# iForgeHat.net
KiCad netlist of a schematic drawn in EAGLE
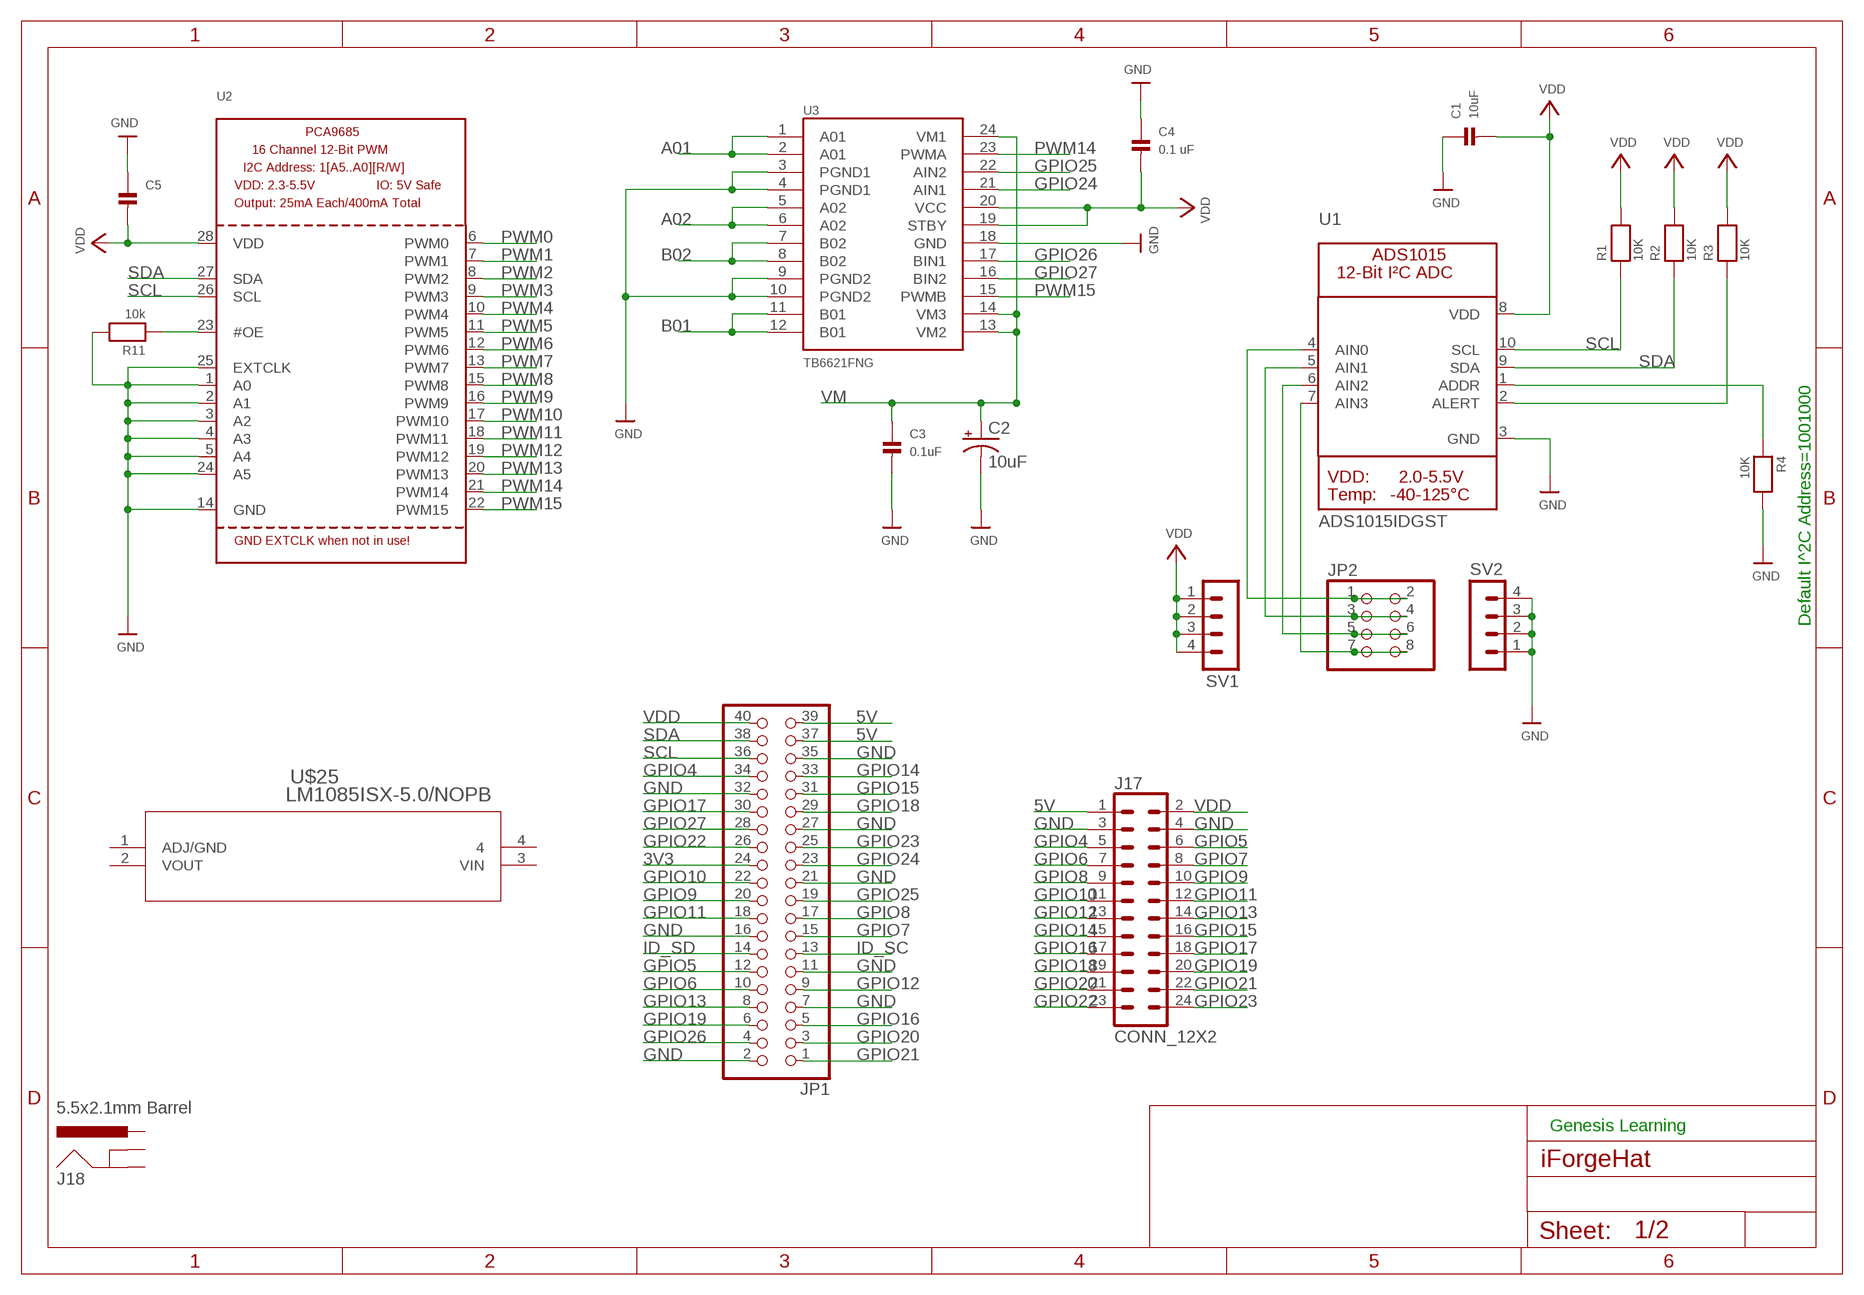
[diagram p0: schematic, sheet 1]
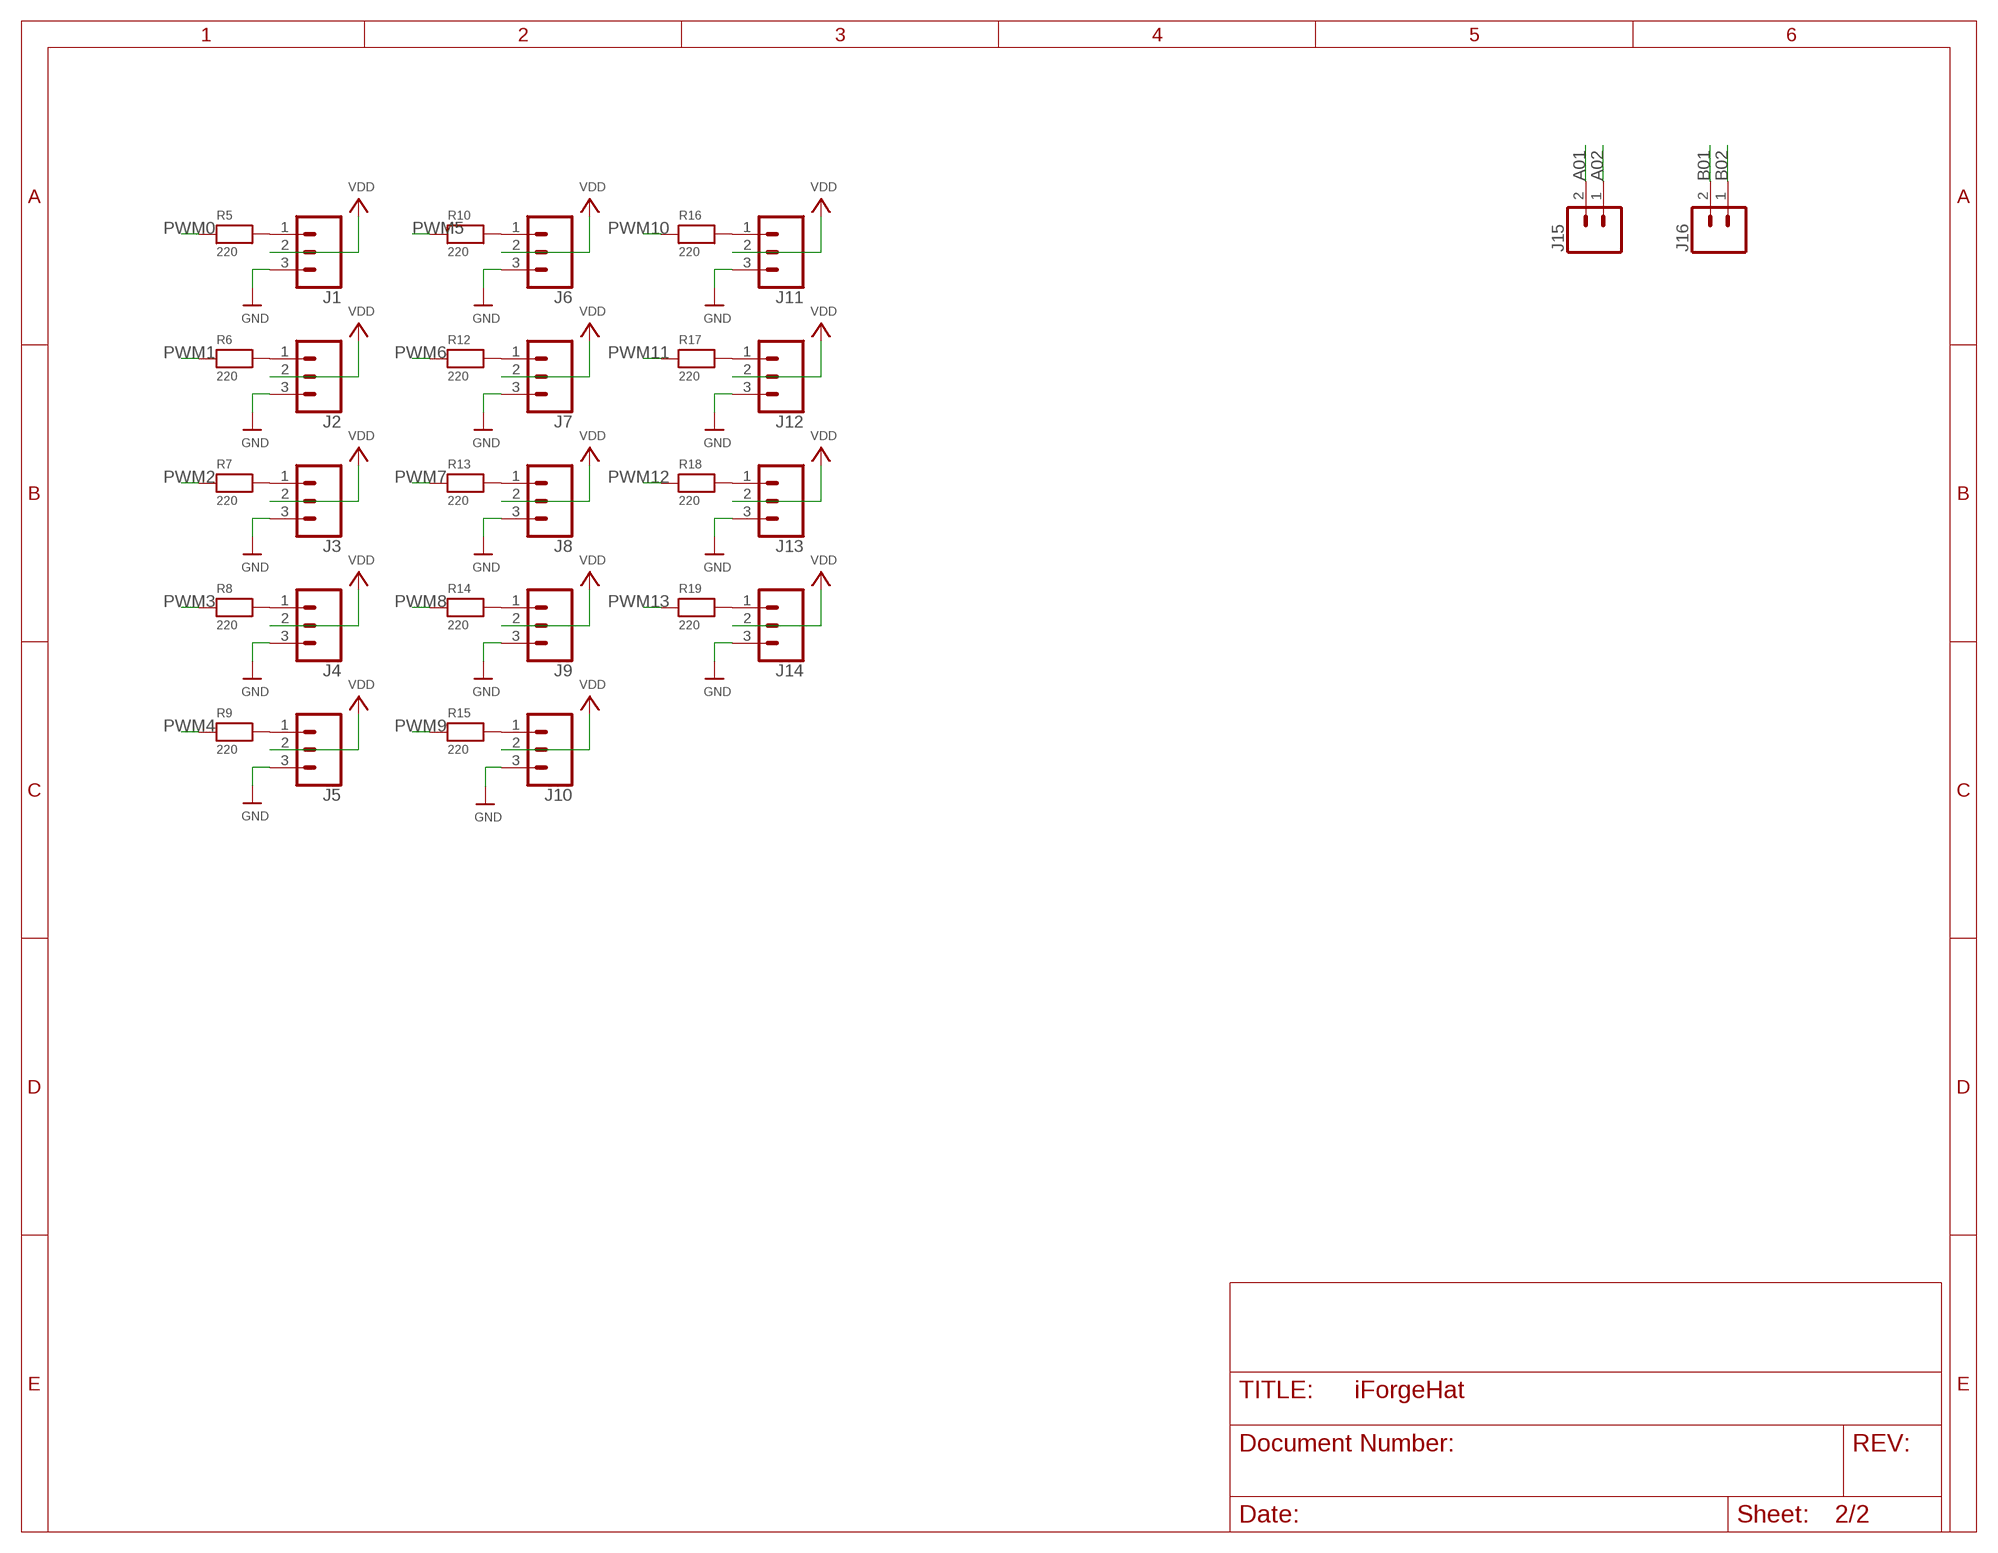
[diagram p1: schematic, sheet 2]

(export (version "E")
  (design (tool "Eeschema 10.0.6"))
  (components
    (comp (ref "J1")
      (value "CONN_03")
      (footprint "eagle-import:1X03")
      (libsource (lib "eagle-import") (part "CONN_03"))
    )
    (comp (ref "J2")
      (value "CONN_03")
      (footprint "eagle-import:1X03")
      (libsource (lib "eagle-import") (part "CONN_03"))
    )
    (comp (ref "J3")
      (value "CONN_03")
      (footprint "eagle-import:1X03")
      (libsource (lib "eagle-import") (part "CONN_03"))
    )
    (comp (ref "J4")
      (value "CONN_03")
      (footprint "eagle-import:1X03")
      (libsource (lib "eagle-import") (part "CONN_03"))
    )
    (comp (ref "J5")
      (value "CONN_03")
      (footprint "eagle-import:1X03")
      (libsource (lib "eagle-import") (part "CONN_03"))
    )
    (comp (ref "J6")
      (value "CONN_03")
      (footprint "eagle-import:1X03")
      (libsource (lib "eagle-import") (part "CONN_03"))
    )
    (comp (ref "J7")
      (value "CONN_03")
      (footprint "eagle-import:1X03")
      (libsource (lib "eagle-import") (part "CONN_03"))
    )
    (comp (ref "J8")
      (value "CONN_03")
      (footprint "eagle-import:1X03")
      (libsource (lib "eagle-import") (part "CONN_03"))
    )
    (comp (ref "J9")
      (value "CONN_03")
      (footprint "eagle-import:1X03")
      (libsource (lib "eagle-import") (part "CONN_03"))
    )
    (comp (ref "J10")
      (value "CONN_03")
      (footprint "eagle-import:1X03")
      (libsource (lib "eagle-import") (part "CONN_03"))
    )
    (comp (ref "J11")
      (value "CONN_03")
      (footprint "eagle-import:1X03")
      (libsource (lib "eagle-import") (part "CONN_03"))
    )
    (comp (ref "J12")
      (value "CONN_03")
      (footprint "eagle-import:1X03")
      (libsource (lib "eagle-import") (part "CONN_03"))
    )
    (comp (ref "J13")
      (value "CONN_03")
      (footprint "eagle-import:1X03")
      (libsource (lib "eagle-import") (part "CONN_03"))
    )
    (comp (ref "J14")
      (value "CONN_03")
      (footprint "eagle-import:1X03")
      (libsource (lib "eagle-import") (part "CONN_03"))
    )
    (comp (ref "J15")
      (value "CONN_02SPRING-2.54-RA")
      (footprint "eagle-import:SPRINGTERMINAL-2.54MM-2")
      (libsource (lib "eagle-import") (part "CONN_02SPRING-2.54-RA"))
    )
    (comp (ref "J16")
      (value "CONN_02SPRING-2.54-RA")
      (footprint "eagle-import:SPRINGTERMINAL-2.54MM-2")
      (libsource (lib "eagle-import") (part "CONN_02SPRING-2.54-RA"))
    )
    (comp (ref "R5")
      (value "220")
      (footprint "eagle-import:0402")
      (libsource (lib "eagle-import") (part "RESISTOR0402"))
    )
    (comp (ref "R6")
      (value "220")
      (footprint "eagle-import:0402")
      (libsource (lib "eagle-import") (part "RESISTOR0402"))
    )
    (comp (ref "R7")
      (value "220")
      (footprint "eagle-import:0402")
      (libsource (lib "eagle-import") (part "RESISTOR0402"))
    )
    (comp (ref "R8")
      (value "220")
      (footprint "eagle-import:0402")
      (libsource (lib "eagle-import") (part "RESISTOR0402"))
    )
    (comp (ref "R9")
      (value "220")
      (footprint "eagle-import:0402")
      (libsource (lib "eagle-import") (part "RESISTOR0402"))
    )
    (comp (ref "R10")
      (value "220")
      (footprint "eagle-import:0402")
      (libsource (lib "eagle-import") (part "RESISTOR0402"))
    )
    (comp (ref "R12")
      (value "220")
      (footprint "eagle-import:0402")
      (libsource (lib "eagle-import") (part "RESISTOR0402"))
    )
    (comp (ref "R13")
      (value "220")
      (footprint "eagle-import:0402")
      (libsource (lib "eagle-import") (part "RESISTOR0402"))
    )
    (comp (ref "R14")
      (value "220")
      (footprint "eagle-import:0402")
      (libsource (lib "eagle-import") (part "RESISTOR0402"))
    )
    (comp (ref "R15")
      (value "220")
      (footprint "eagle-import:0402")
      (libsource (lib "eagle-import") (part "RESISTOR0402"))
    )
    (comp (ref "R16")
      (value "220")
      (footprint "eagle-import:0402")
      (libsource (lib "eagle-import") (part "RESISTOR0402"))
    )
    (comp (ref "R17")
      (value "220")
      (footprint "eagle-import:0402")
      (libsource (lib "eagle-import") (part "RESISTOR0402"))
    )
    (comp (ref "R18")
      (value "220")
      (footprint "eagle-import:0402")
      (libsource (lib "eagle-import") (part "RESISTOR0402"))
    )
    (comp (ref "R19")
      (value "220")
      (footprint "eagle-import:0402")
      (libsource (lib "eagle-import") (part "RESISTOR0402"))
    )
    (comp (ref "C1")
      (value "10uF")
      (footprint "eagle-import:0402")
      (libsource (lib "eagle-import") (part "CAP_CERAMIC0402"))
    )
    (comp (ref "C2")
      (value "10uF")
      (footprint "eagle-import:414-VA5R")
      (libsource (lib "eagle-import") (part "SUPERCAP"))
    )
    (comp (ref "C3")
      (value "0.1uF")
      (footprint "eagle-import:0402")
      (libsource (lib "eagle-import") (part "CAP_CERAMIC0402"))
    )
    (comp (ref "C4")
      (value "0.1 uF")
      (footprint "eagle-import:0402")
      (libsource (lib "eagle-import") (part "CAP_CERAMIC0402"))
    )
    (comp (ref "C5")
      (value "CAP_CERAMIC0402")
      (footprint "eagle-import:0402")
      (libsource (lib "eagle-import") (part "CAP_CERAMIC0402"))
    )
    (comp (ref "J17")
      (value "CONN_12X2")
      (footprint "eagle-import:2X12")
      (libsource (lib "eagle-import") (part "CONN_12X2"))
    )
    (comp (ref "J18")
      (value "5.5x2.1mm Barrel")
      (footprint "eagle-import:POWER_JACK_SMD")
      (libsource (lib "eagle-import") (part "POWER_JACKSMD"))
    )
    (comp (ref "JP1")
      (value "PINHD-2X20")
      (footprint "eagle-import:2X20")
      (libsource (lib "eagle-import") (part "PINHD-2X20"))
    )
    (comp (ref "JP2")
      (value "PINHD-2X4")
      (footprint "eagle-import:2X04")
      (libsource (lib "eagle-import") (part "PINHD-2X4"))
    )
    (comp (ref "R1")
      (value "10K")
      (footprint "eagle-import:0402")
      (libsource (lib "eagle-import") (part "RESISTOR0402"))
    )
    (comp (ref "R2")
      (value "10K")
      (footprint "eagle-import:0402")
      (libsource (lib "eagle-import") (part "RESISTOR0402"))
    )
    (comp (ref "R3")
      (value "10K")
      (footprint "eagle-import:0402")
      (libsource (lib "eagle-import") (part "RESISTOR0402"))
    )
    (comp (ref "R4")
      (value "10K")
      (footprint "eagle-import:0402")
      (libsource (lib "eagle-import") (part "RESISTOR0402"))
    )
    (comp (ref "R11")
      (value "10k")
      (footprint "eagle-import:0402")
      (libsource (lib "eagle-import") (part "RESISTOR0402"))
    )
    (comp (ref "SV1")
      (value "MA04-1")
      (footprint "eagle-import:MA04-1")
      (libsource (lib "eagle-import") (part "MA04-1"))
    )
    (comp (ref "SV2")
      (value "MA04-1")
      (footprint "eagle-import:MA04-1")
      (libsource (lib "eagle-import") (part "MA04-1"))
    )
    (comp (ref "U$25")
      (value "LM1085ISX-5.0/NOPB")
      (footprint "eagle-import:TS3B")
      (fields (field (name "MANUFACTURER_PART_NUMBER") "LM1085ISX5.0NOPB"))
      (libsource (lib "eagle-import") (part "LM1085ISX-5.0/NOPB"))
    )
    (comp (ref "U1")
      (value "ADS1015IDGST")
      (footprint "eagle-import:MSOP10")
      (libsource (lib "eagle-import") (part "ADC_ADS1015"))
    )
    (comp (ref "U2")
      (value "PCA9685")
      (footprint "eagle-import:TSSOP28")
      (libsource (lib "eagle-import") (part "PCA9685"))
    )
    (comp (ref "U3")
      (value "TB6621FNG")
      (footprint "eagle-import:SSOP24")
      (libsource (lib "eagle-import") (part "TB6621FNG"))
    )
  )
  (nets
    (net (code "1") (name "3V3") (class "Default")
      (node (ref "JP1") (pin "24") (pinfunction "24_24") (pintype "passive"))
    )
    (net (code "2") (name "5V") (class "Default")
      (node (ref "J17") (pin "1") (pinfunction "1_1") (pintype "passive"))
      (node (ref "JP1") (pin "37") (pinfunction "37_37") (pintype "passive"))
      (node (ref "JP1") (pin "39") (pinfunction "39_39") (pintype "passive"))
    )
    (net (code "3") (name "A01") (class "Default")
      (node (ref "J15") (pin "2") (pinfunction "2_2") (pintype "passive"))
      (node (ref "U3") (pin "1") (pinfunction "A01_1") (pintype "bidirectional"))
      (node (ref "U3") (pin "2") (pinfunction "A01_2") (pintype "bidirectional"))
    )
    (net (code "4") (name "A02") (class "Default")
      (node (ref "J15") (pin "1") (pinfunction "1_1") (pintype "passive"))
      (node (ref "U3") (pin "5") (pinfunction "A02_5") (pintype "bidirectional"))
      (node (ref "U3") (pin "6") (pinfunction "A02_6") (pintype "bidirectional"))
    )
    (net (code "5") (name "B01") (class "Default")
      (node (ref "J16") (pin "2") (pinfunction "2_2") (pintype "passive"))
      (node (ref "U3") (pin "11") (pinfunction "B01_11") (pintype "bidirectional"))
      (node (ref "U3") (pin "12") (pinfunction "B01_12") (pintype "bidirectional"))
    )
    (net (code "6") (name "B02") (class "Default")
      (node (ref "J16") (pin "1") (pinfunction "1_1") (pintype "passive"))
      (node (ref "U3") (pin "7") (pinfunction "B02_7") (pintype "bidirectional"))
      (node (ref "U3") (pin "8") (pinfunction "B02_8") (pintype "bidirectional"))
    )
    (net (code "7") (name "GND") (class "Default")
      (node (ref "C1") (pin "1") (pinfunction "P$1_1") (pintype "passive"))
      (node (ref "C2") (pin "-") (pinfunction "-_-") (pintype "passive"))
      (node (ref "C3") (pin "2") (pinfunction "P$2_2") (pintype "passive"))
      (node (ref "C4") (pin "1") (pinfunction "P$1_1") (pintype "passive"))
      (node (ref "C5") (pin "1") (pinfunction "P$1_1") (pintype "passive"))
      (node (ref "J1") (pin "3") (pinfunction "3_3") (pintype "passive"))
      (node (ref "J10") (pin "3") (pinfunction "3_3") (pintype "passive"))
      (node (ref "J11") (pin "3") (pinfunction "3_3") (pintype "passive"))
      (node (ref "J12") (pin "3") (pinfunction "3_3") (pintype "passive"))
      (node (ref "J13") (pin "3") (pinfunction "3_3") (pintype "passive"))
      (node (ref "J14") (pin "3") (pinfunction "3_3") (pintype "passive"))
      (node (ref "J17") (pin "3") (pinfunction "3_3") (pintype "passive"))
      (node (ref "J17") (pin "4") (pinfunction "4_4") (pintype "passive"))
      (node (ref "J2") (pin "3") (pinfunction "3_3") (pintype "passive"))
      (node (ref "J3") (pin "3") (pinfunction "3_3") (pintype "passive"))
      (node (ref "J4") (pin "3") (pinfunction "3_3") (pintype "passive"))
      (node (ref "J5") (pin "3") (pinfunction "3_3") (pintype "passive"))
      (node (ref "J6") (pin "3") (pinfunction "3_3") (pintype "passive"))
      (node (ref "J7") (pin "3") (pinfunction "3_3") (pintype "passive"))
      (node (ref "J8") (pin "3") (pinfunction "3_3") (pintype "passive"))
      (node (ref "J9") (pin "3") (pinfunction "3_3") (pintype "passive"))
      (node (ref "JP1") (pin "11") (pinfunction "11_11") (pintype "passive"))
      (node (ref "JP1") (pin "16") (pinfunction "16_16") (pintype "passive"))
      (node (ref "JP1") (pin "2") (pinfunction "2_2") (pintype "passive"))
      (node (ref "JP1") (pin "21") (pinfunction "21_21") (pintype "passive"))
      (node (ref "JP1") (pin "27") (pinfunction "27_27") (pintype "passive"))
      (node (ref "JP1") (pin "32") (pinfunction "32_32") (pintype "passive"))
      (node (ref "JP1") (pin "35") (pinfunction "35_35") (pintype "passive"))
      (node (ref "JP1") (pin "7") (pinfunction "7_7") (pintype "passive"))
      (node (ref "R11") (pin "2") (pinfunction "2_2") (pintype "passive"))
      (node (ref "R4") (pin "2") (pinfunction "2_2") (pintype "passive"))
      (node (ref "SV2") (pin "1") (pinfunction "1_1") (pintype "passive"))
      (node (ref "SV2") (pin "2") (pinfunction "2_2") (pintype "passive"))
      (node (ref "SV2") (pin "3") (pinfunction "3_3") (pintype "passive"))
      (node (ref "SV2") (pin "4") (pinfunction "4_4") (pintype "passive"))
      (node (ref "U1") (pin "3") (pinfunction "GND_3") (pintype "bidirectional"))
      (node (ref "U2") (pin "1") (pinfunction "A0_1") (pintype "bidirectional"))
      (node (ref "U2") (pin "14") (pinfunction "GND_14") (pintype "power_in"))
      (node (ref "U2") (pin "2") (pinfunction "A1_2") (pintype "bidirectional"))
      (node (ref "U2") (pin "24") (pinfunction "A5_24") (pintype "bidirectional"))
      (node (ref "U2") (pin "25") (pinfunction "EXTCLK_25") (pintype "input"))
      (node (ref "U2") (pin "3") (pinfunction "A2_3") (pintype "bidirectional"))
      (node (ref "U2") (pin "4") (pinfunction "A3_4") (pintype "bidirectional"))
      (node (ref "U2") (pin "5") (pinfunction "A4_5") (pintype "bidirectional"))
      (node (ref "U3") (pin "10") (pinfunction "PGND2_10") (pintype "bidirectional"))
      (node (ref "U3") (pin "18") (pinfunction "GND_18") (pintype "bidirectional"))
      (node (ref "U3") (pin "3") (pinfunction "PGND1_3") (pintype "bidirectional"))
      (node (ref "U3") (pin "4") (pinfunction "PGND1_4") (pintype "bidirectional"))
      (node (ref "U3") (pin "9") (pinfunction "PGND2_9") (pintype "bidirectional"))
    )
    (net (code "8") (name "GPIO4") (class "Default")
      (node (ref "J17") (pin "5") (pinfunction "5_5") (pintype "passive"))
      (node (ref "JP1") (pin "34") (pinfunction "34_34") (pintype "passive"))
    )
    (net (code "9") (name "GPIO5") (class "Default")
      (node (ref "J17") (pin "6") (pinfunction "6_6") (pintype "passive"))
      (node (ref "JP1") (pin "12") (pinfunction "12_12") (pintype "passive"))
    )
    (net (code "10") (name "GPIO6") (class "Default")
      (node (ref "J17") (pin "7") (pinfunction "7_7") (pintype "passive"))
      (node (ref "JP1") (pin "10") (pinfunction "10_10") (pintype "passive"))
    )
    (net (code "11") (name "GPIO7") (class "Default")
      (node (ref "J17") (pin "8") (pinfunction "8_8") (pintype "passive"))
      (node (ref "JP1") (pin "15") (pinfunction "15_15") (pintype "passive"))
    )
    (net (code "12") (name "GPIO8") (class "Default")
      (node (ref "J17") (pin "9") (pinfunction "9_9") (pintype "passive"))
      (node (ref "JP1") (pin "17") (pinfunction "17_17") (pintype "passive"))
    )
    (net (code "13") (name "GPIO9") (class "Default")
      (node (ref "J17") (pin "10") (pinfunction "10_10") (pintype "passive"))
      (node (ref "JP1") (pin "20") (pinfunction "20_20") (pintype "passive"))
    )
    (net (code "14") (name "GPIO10") (class "Default")
      (node (ref "J17") (pin "11") (pinfunction "11_11") (pintype "passive"))
      (node (ref "JP1") (pin "22") (pinfunction "22_22") (pintype "passive"))
    )
    (net (code "15") (name "GPIO11") (class "Default")
      (node (ref "J17") (pin "12") (pinfunction "12_12") (pintype "passive"))
      (node (ref "JP1") (pin "18") (pinfunction "18_18") (pintype "passive"))
    )
    (net (code "16") (name "GPIO12") (class "Default")
      (node (ref "J17") (pin "13") (pinfunction "13_13") (pintype "passive"))
      (node (ref "JP1") (pin "9") (pinfunction "9_9") (pintype "passive"))
    )
    (net (code "17") (name "GPIO13") (class "Default")
      (node (ref "J17") (pin "14") (pinfunction "14_14") (pintype "passive"))
      (node (ref "JP1") (pin "8") (pinfunction "8_8") (pintype "passive"))
    )
    (net (code "18") (name "GPIO14") (class "Default")
      (node (ref "J17") (pin "15") (pinfunction "15_15") (pintype "passive"))
      (node (ref "JP1") (pin "33") (pinfunction "33_33") (pintype "passive"))
    )
    (net (code "19") (name "GPIO15") (class "Default")
      (node (ref "J17") (pin "16") (pinfunction "16_16") (pintype "passive"))
      (node (ref "JP1") (pin "31") (pinfunction "31_31") (pintype "passive"))
    )
    (net (code "20") (name "GPIO16") (class "Default")
      (node (ref "J17") (pin "17") (pinfunction "17_17") (pintype "passive"))
      (node (ref "JP1") (pin "5") (pinfunction "5_5") (pintype "passive"))
    )
    (net (code "21") (name "GPIO17") (class "Default")
      (node (ref "J17") (pin "18") (pinfunction "18_18") (pintype "passive"))
      (node (ref "JP1") (pin "30") (pinfunction "30_30") (pintype "passive"))
    )
    (net (code "22") (name "GPIO18") (class "Default")
      (node (ref "J17") (pin "19") (pinfunction "19_19") (pintype "passive"))
      (node (ref "JP1") (pin "29") (pinfunction "29_29") (pintype "passive"))
    )
    (net (code "23") (name "GPIO19") (class "Default")
      (node (ref "J17") (pin "20") (pinfunction "20_20") (pintype "passive"))
      (node (ref "JP1") (pin "6") (pinfunction "6_6") (pintype "passive"))
    )
    (net (code "24") (name "GPIO20") (class "Default")
      (node (ref "J17") (pin "21") (pinfunction "21_21") (pintype "passive"))
      (node (ref "JP1") (pin "3") (pinfunction "3_3") (pintype "passive"))
    )
    (net (code "25") (name "GPIO21") (class "Default")
      (node (ref "J17") (pin "22") (pinfunction "22_22") (pintype "passive"))
      (node (ref "JP1") (pin "1") (pinfunction "1_1") (pintype "passive"))
    )
    (net (code "26") (name "GPIO22") (class "Default")
      (node (ref "J17") (pin "23") (pinfunction "23_23") (pintype "passive"))
      (node (ref "JP1") (pin "26") (pinfunction "26_26") (pintype "passive"))
    )
    (net (code "27") (name "GPIO23") (class "Default")
      (node (ref "J17") (pin "24") (pinfunction "24_24") (pintype "passive"))
      (node (ref "JP1") (pin "25") (pinfunction "25_25") (pintype "passive"))
    )
    (net (code "28") (name "GPIO24") (class "Default")
      (node (ref "JP1") (pin "23") (pinfunction "23_23") (pintype "passive"))
      (node (ref "U3") (pin "21") (pinfunction "AIN1_21") (pintype "bidirectional"))
    )
    (net (code "29") (name "GPIO25") (class "Default")
      (node (ref "JP1") (pin "19") (pinfunction "19_19") (pintype "passive"))
      (node (ref "U3") (pin "22") (pinfunction "AIN2_22") (pintype "bidirectional"))
    )
    (net (code "30") (name "GPIO26") (class "Default")
      (node (ref "JP1") (pin "4") (pinfunction "4_4") (pintype "passive"))
      (node (ref "U3") (pin "17") (pinfunction "BIN1_17") (pintype "bidirectional"))
    )
    (net (code "31") (name "GPIO27") (class "Default")
      (node (ref "JP1") (pin "28") (pinfunction "28_28") (pintype "passive"))
      (node (ref "U3") (pin "16") (pinfunction "BIN2_16") (pintype "bidirectional"))
    )
    (net (code "32") (name "ID_SC") (class "Default")
      (node (ref "JP1") (pin "13") (pinfunction "13_13") (pintype "passive"))
    )
    (net (code "33") (name "ID_SD") (class "Default")
      (node (ref "JP1") (pin "14") (pinfunction "14_14") (pintype "passive"))
    )
    (net (code "34") (name "Net-(J1-Pad1)") (class "Default")
      (node (ref "J1") (pin "1") (pinfunction "1_1") (pintype "passive"))
      (node (ref "R5") (pin "2") (pinfunction "2_2") (pintype "passive"))
    )
    (net (code "35") (name "Net-(J2-Pad1)") (class "Default")
      (node (ref "J2") (pin "1") (pinfunction "1_1") (pintype "passive"))
      (node (ref "R6") (pin "2") (pinfunction "2_2") (pintype "passive"))
    )
    (net (code "36") (name "Net-(J3-Pad1)") (class "Default")
      (node (ref "J3") (pin "1") (pinfunction "1_1") (pintype "passive"))
      (node (ref "R7") (pin "2") (pinfunction "2_2") (pintype "passive"))
    )
    (net (code "37") (name "Net-(J4-Pad1)") (class "Default")
      (node (ref "J4") (pin "1") (pinfunction "1_1") (pintype "passive"))
      (node (ref "R8") (pin "2") (pinfunction "2_2") (pintype "passive"))
    )
    (net (code "38") (name "Net-(J5-Pad1)") (class "Default")
      (node (ref "J5") (pin "1") (pinfunction "1_1") (pintype "passive"))
      (node (ref "R9") (pin "2") (pinfunction "2_2") (pintype "passive"))
    )
    (net (code "39") (name "Net-(J6-Pad1)") (class "Default")
      (node (ref "J6") (pin "1") (pinfunction "1_1") (pintype "passive"))
      (node (ref "R10") (pin "2") (pinfunction "2_2") (pintype "passive"))
    )
    (net (code "40") (name "Net-(J7-Pad1)") (class "Default")
      (node (ref "J7") (pin "1") (pinfunction "1_1") (pintype "passive"))
      (node (ref "R12") (pin "2") (pinfunction "2_2") (pintype "passive"))
    )
    (net (code "41") (name "Net-(J8-Pad1)") (class "Default")
      (node (ref "J8") (pin "1") (pinfunction "1_1") (pintype "passive"))
      (node (ref "R13") (pin "2") (pinfunction "2_2") (pintype "passive"))
    )
    (net (code "42") (name "Net-(J9-Pad1)") (class "Default")
      (node (ref "J9") (pin "1") (pinfunction "1_1") (pintype "passive"))
      (node (ref "R14") (pin "2") (pinfunction "2_2") (pintype "passive"))
    )
    (net (code "43") (name "Net-(J10-Pad1)") (class "Default")
      (node (ref "J10") (pin "1") (pinfunction "1_1") (pintype "passive"))
      (node (ref "R15") (pin "2") (pinfunction "2_2") (pintype "passive"))
    )
    (net (code "44") (name "Net-(J11-Pad1)") (class "Default")
      (node (ref "J11") (pin "1") (pinfunction "1_1") (pintype "passive"))
      (node (ref "R16") (pin "2") (pinfunction "2_2") (pintype "passive"))
    )
    (net (code "45") (name "Net-(J12-Pad1)") (class "Default")
      (node (ref "J12") (pin "1") (pinfunction "1_1") (pintype "passive"))
      (node (ref "R17") (pin "2") (pinfunction "2_2") (pintype "passive"))
    )
    (net (code "46") (name "Net-(J13-Pad1)") (class "Default")
      (node (ref "J13") (pin "1") (pinfunction "1_1") (pintype "passive"))
      (node (ref "R18") (pin "2") (pinfunction "2_2") (pintype "passive"))
    )
    (net (code "47") (name "Net-(J14-Pad1)") (class "Default")
      (node (ref "J14") (pin "1") (pinfunction "1_1") (pintype "passive"))
      (node (ref "R19") (pin "2") (pinfunction "2_2") (pintype "passive"))
    )
    (net (code "48") (name "Net-(U1-ADDR)") (class "Default")
      (node (ref "R4") (pin "1") (pinfunction "1_1") (pintype "passive"))
      (node (ref "U1") (pin "1") (pinfunction "ADDR_1") (pintype "bidirectional"))
    )
    (net (code "49") (name "Net-(U1-AIN0)") (class "Default")
      (node (ref "JP2") (pin "1") (pinfunction "1_1") (pintype "passive"))
      (node (ref "JP2") (pin "2") (pinfunction "2_2") (pintype "passive"))
      (node (ref "U1") (pin "4") (pinfunction "AIN0_4") (pintype "bidirectional"))
    )
    (net (code "50") (name "Net-(U1-AIN1)") (class "Default")
      (node (ref "JP2") (pin "3") (pinfunction "3_3") (pintype "passive"))
      (node (ref "JP2") (pin "4") (pinfunction "4_4") (pintype "passive"))
      (node (ref "U1") (pin "5") (pinfunction "AIN1_5") (pintype "bidirectional"))
    )
    (net (code "51") (name "Net-(U1-AIN2)") (class "Default")
      (node (ref "JP2") (pin "5") (pinfunction "5_5") (pintype "passive"))
      (node (ref "JP2") (pin "6") (pinfunction "6_6") (pintype "passive"))
      (node (ref "U1") (pin "6") (pinfunction "AIN2_6") (pintype "bidirectional"))
    )
    (net (code "52") (name "Net-(U1-AIN3)") (class "Default")
      (node (ref "JP2") (pin "7") (pinfunction "7_7") (pintype "passive"))
      (node (ref "JP2") (pin "8") (pinfunction "8_8") (pintype "passive"))
      (node (ref "U1") (pin "7") (pinfunction "AIN3_7") (pintype "bidirectional"))
    )
    (net (code "53") (name "Net-(U1-ALERT)") (class "Default")
      (node (ref "R3") (pin "1") (pinfunction "1_1") (pintype "passive"))
      (node (ref "U1") (pin "2") (pinfunction "ALERT_2") (pintype "bidirectional"))
    )
    (net (code "54") (name "Net-(U2-#OE)") (class "Default")
      (node (ref "R11") (pin "1") (pinfunction "1_1") (pintype "passive"))
      (node (ref "U2") (pin "23") (pinfunction "#OE_23") (pintype "input"))
    )
    (net (code "55") (name "PWM0") (class "Default")
      (node (ref "R5") (pin "1") (pinfunction "1_1") (pintype "passive"))
      (node (ref "U2") (pin "6") (pinfunction "PWM0_6") (pintype "output"))
    )
    (net (code "56") (name "PWM1") (class "Default")
      (node (ref "R6") (pin "1") (pinfunction "1_1") (pintype "passive"))
      (node (ref "U2") (pin "7") (pinfunction "PWM1_7") (pintype "output"))
    )
    (net (code "57") (name "PWM2") (class "Default")
      (node (ref "R7") (pin "1") (pinfunction "1_1") (pintype "passive"))
      (node (ref "U2") (pin "8") (pinfunction "PWM2_8") (pintype "output"))
    )
    (net (code "58") (name "PWM3") (class "Default")
      (node (ref "R8") (pin "1") (pinfunction "1_1") (pintype "passive"))
      (node (ref "U2") (pin "9") (pinfunction "PWM3_9") (pintype "output"))
    )
    (net (code "59") (name "PWM4") (class "Default")
      (node (ref "R9") (pin "1") (pinfunction "1_1") (pintype "passive"))
      (node (ref "U2") (pin "10") (pinfunction "PWM4_10") (pintype "output"))
    )
    (net (code "60") (name "PWM5") (class "Default")
      (node (ref "R10") (pin "1") (pinfunction "1_1") (pintype "passive"))
      (node (ref "U2") (pin "11") (pinfunction "PWM5_11") (pintype "output"))
    )
    (net (code "61") (name "PWM6") (class "Default")
      (node (ref "R12") (pin "1") (pinfunction "1_1") (pintype "passive"))
      (node (ref "U2") (pin "12") (pinfunction "PWM6_12") (pintype "output"))
    )
    (net (code "62") (name "PWM7") (class "Default")
      (node (ref "R13") (pin "1") (pinfunction "1_1") (pintype "passive"))
      (node (ref "U2") (pin "13") (pinfunction "PWM7_13") (pintype "output"))
    )
    (net (code "63") (name "PWM8") (class "Default")
      (node (ref "R14") (pin "1") (pinfunction "1_1") (pintype "passive"))
      (node (ref "U2") (pin "15") (pinfunction "PWM8_15") (pintype "output"))
    )
    (net (code "64") (name "PWM9") (class "Default")
      (node (ref "R15") (pin "1") (pinfunction "1_1") (pintype "passive"))
      (node (ref "U2") (pin "16") (pinfunction "PWM9_16") (pintype "output"))
    )
    (net (code "65") (name "PWM10") (class "Default")
      (node (ref "R16") (pin "1") (pinfunction "1_1") (pintype "passive"))
      (node (ref "U2") (pin "17") (pinfunction "PWM10_17") (pintype "output"))
    )
    (net (code "66") (name "PWM11") (class "Default")
      (node (ref "R17") (pin "1") (pinfunction "1_1") (pintype "passive"))
      (node (ref "U2") (pin "18") (pinfunction "PWM11_18") (pintype "output"))
    )
    (net (code "67") (name "PWM12") (class "Default")
      (node (ref "R18") (pin "1") (pinfunction "1_1") (pintype "passive"))
      (node (ref "U2") (pin "19") (pinfunction "PWM12_19") (pintype "output"))
    )
    (net (code "68") (name "PWM13") (class "Default")
      (node (ref "R19") (pin "1") (pinfunction "1_1") (pintype "passive"))
      (node (ref "U2") (pin "20") (pinfunction "PWM13_20") (pintype "output"))
    )
    (net (code "69") (name "PWM14") (class "Default")
      (node (ref "U2") (pin "21") (pinfunction "PWM14_21") (pintype "output"))
      (node (ref "U3") (pin "23") (pinfunction "PWMA_23") (pintype "bidirectional"))
    )
    (net (code "70") (name "PWM15") (class "Default")
      (node (ref "U2") (pin "22") (pinfunction "PWM15_22") (pintype "output"))
      (node (ref "U3") (pin "15") (pinfunction "PWMB_15") (pintype "bidirectional"))
    )
    (net (code "71") (name "SCL") (class "Default")
      (node (ref "JP1") (pin "36") (pinfunction "36_36") (pintype "passive"))
      (node (ref "R1") (pin "1") (pinfunction "1_1") (pintype "passive"))
      (node (ref "U1") (pin "10") (pinfunction "SCL_10") (pintype "bidirectional"))
      (node (ref "U2") (pin "26") (pinfunction "SCL_26") (pintype "bidirectional"))
    )
    (net (code "72") (name "SDA") (class "Default")
      (node (ref "JP1") (pin "38") (pinfunction "38_38") (pintype "passive"))
      (node (ref "R2") (pin "1") (pinfunction "1_1") (pintype "passive"))
      (node (ref "U1") (pin "9") (pinfunction "SDA_9") (pintype "bidirectional"))
      (node (ref "U2") (pin "27") (pinfunction "SDA_27") (pintype "bidirectional"))
    )
    (net (code "73") (name "VDD") (class "Default")
      (node (ref "C1") (pin "2") (pinfunction "P$2_2") (pintype "passive"))
      (node (ref "C4") (pin "2") (pinfunction "P$2_2") (pintype "passive"))
      (node (ref "C5") (pin "2") (pinfunction "P$2_2") (pintype "passive"))
      (node (ref "J1") (pin "2") (pinfunction "2_2") (pintype "passive"))
      (node (ref "J10") (pin "2") (pinfunction "2_2") (pintype "passive"))
      (node (ref "J11") (pin "2") (pinfunction "2_2") (pintype "passive"))
      (node (ref "J12") (pin "2") (pinfunction "2_2") (pintype "passive"))
      (node (ref "J13") (pin "2") (pinfunction "2_2") (pintype "passive"))
      (node (ref "J14") (pin "2") (pinfunction "2_2") (pintype "passive"))
      (node (ref "J17") (pin "2") (pinfunction "2_2") (pintype "passive"))
      (node (ref "J2") (pin "2") (pinfunction "2_2") (pintype "passive"))
      (node (ref "J3") (pin "2") (pinfunction "2_2") (pintype "passive"))
      (node (ref "J4") (pin "2") (pinfunction "2_2") (pintype "passive"))
      (node (ref "J5") (pin "2") (pinfunction "2_2") (pintype "passive"))
      (node (ref "J6") (pin "2") (pinfunction "2_2") (pintype "passive"))
      (node (ref "J7") (pin "2") (pinfunction "2_2") (pintype "passive"))
      (node (ref "J8") (pin "2") (pinfunction "2_2") (pintype "passive"))
      (node (ref "J9") (pin "2") (pinfunction "2_2") (pintype "passive"))
      (node (ref "JP1") (pin "40") (pinfunction "40_40") (pintype "passive"))
      (node (ref "R1") (pin "2") (pinfunction "2_2") (pintype "passive"))
      (node (ref "R2") (pin "2") (pinfunction "2_2") (pintype "passive"))
      (node (ref "R3") (pin "2") (pinfunction "2_2") (pintype "passive"))
      (node (ref "SV1") (pin "1") (pinfunction "1_1") (pintype "passive"))
      (node (ref "SV1") (pin "2") (pinfunction "2_2") (pintype "passive"))
      (node (ref "SV1") (pin "3") (pinfunction "3_3") (pintype "passive"))
      (node (ref "SV1") (pin "4") (pinfunction "4_4") (pintype "passive"))
      (node (ref "U1") (pin "8") (pinfunction "VDD_8") (pintype "bidirectional"))
      (node (ref "U2") (pin "28") (pinfunction "VDD_28") (pintype "power_in"))
      (node (ref "U3") (pin "19") (pinfunction "STBY_19") (pintype "bidirectional"))
      (node (ref "U3") (pin "20") (pinfunction "VCC_20") (pintype "bidirectional"))
    )
    (net (code "74") (name "VM") (class "Default")
      (node (ref "C2") (pin "+") (pinfunction "+_+") (pintype "passive"))
      (node (ref "C3") (pin "1") (pinfunction "P$1_1") (pintype "passive"))
      (node (ref "U3") (pin "13") (pinfunction "VM2_13") (pintype "bidirectional"))
      (node (ref "U3") (pin "14") (pinfunction "VM3_14") (pintype "bidirectional"))
      (node (ref "U3") (pin "24") (pinfunction "VM1_24") (pintype "bidirectional"))
    )
    (net (code "75") (name "unconnected-(J18-GND-PadP$4)") (class "Default")
      (node (ref "J18") (pin "P$4") (pinfunction "GND_P$4") (pintype "bidirectional"))
    )
    (net (code "76") (name "unconnected-(J18-GNDBREAK-PadGND)") (class "Default")
      (node (ref "J18") (pin "GND") (pinfunction "GNDBREAK_GND") (pintype "bidirectional"))
    )
    (net (code "77") (name "unconnected-(J18-PWR-PadVIN0)") (class "Default")
      (node (ref "J18") (pin "VIN0") (pinfunction "PWR_VIN0") (pintype "bidirectional"))
    )
    (net (code "78") (name "unconnected-(U$25-ADJ{slash}GND-Pad1)") (class "Default")
      (node (ref "U$25") (pin "1") (pinfunction "ADJ/GND_1") (pintype "passive"))
    )
    (net (code "79") (name "unconnected-(U$25-Pad4)") (class "Default")
      (node (ref "U$25") (pin "4") (pinfunction "4_4") (pintype "passive"))
    )
    (net (code "80") (name "unconnected-(U$25-VIN-Pad3)") (class "Default")
      (node (ref "U$25") (pin "3") (pinfunction "VIN_3") (pintype "input"))
    )
    (net (code "81") (name "unconnected-(U$25-VOUT-Pad2)") (class "Default")
      (node (ref "U$25") (pin "2") (pinfunction "VOUT_2") (pintype "output"))
    )
  )
)
